# School_System.net
KiCad netlist of a schematic drawn in EAGLE
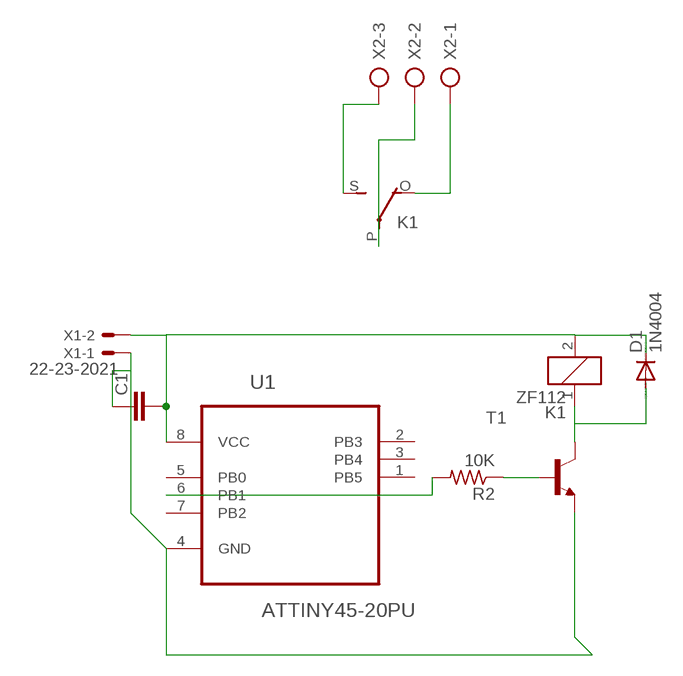
[diagram p0: schematic, sheet 1]

(export (version "E")
  (design (tool "Eeschema 10.0.6"))
  (components
    (comp (ref "C1")
      (value "C2,5-3")
      (footprint "eagle-import:C2.5-3")
      (libsource (lib "eagle-import") (part "C2,5-3"))
    )
    (comp (ref "D1")
      (value "1N4004")
      (footprint "eagle-import:DO41-10")
      (libsource (lib "eagle-import") (part "1N4004"))
    )
    (comp (ref "K1")
      (value "ZF112")
      (footprint "eagle-import:ZF112")
      (libsource (lib "eagle-import") (part "ZF112"))
    )
    (comp (ref "R2")
      (value "10K")
      (footprint "eagle-import:0204_7")
      (libsource (lib "eagle-import") (part "R-US_0204/7"))
    )
    (comp (ref "T1")
      (value "2N2222-NPN-TO92-EBC")
      (footprint "eagle-import:TO92-EBC")
      (libsource (lib "eagle-import") (part "-NPN-TO92-EBC2N2222"))
    )
    (comp (ref "U1")
      (value "ATTINY45-20PU")
      (footprint "eagle-import:DIP254P762X533-8")
      (libsource (lib "eagle-import") (part "ATTINY45-20PU"))
    )
    (comp (ref "X1")
      (value "22-23-2021")
      (footprint "eagle-import:22-23-2021")
      (fields (field (name "MF") "MOLEX"))
      (libsource (lib "eagle-import") (part "22-23-2021"))
    )
    (comp (ref "X2")
      (value "AK300/3")
      (footprint "eagle-import:AK300_3")
      (libsource (lib "eagle-import") (part "AK300/3"))
    )
  )
  (nets
    (net (code "1") (name "Net-(D1-PadA)") (class "Default")
      (node (ref "D1") (pin "A") (pinfunction "A_A") (pintype "passive"))
      (node (ref "K1") (pin "1") (pinfunction "1_1") (pintype "passive"))
      (node (ref "T1") (pin "C") (pinfunction "C_C") (pintype "passive"))
    )
    (net (code "2") (name "Net-(R2-Pad1)") (class "Default")
      (node (ref "R2") (pin "1") (pinfunction "1_1") (pintype "passive"))
      (node (ref "T1") (pin "B") (pinfunction "B_B") (pintype "passive"))
    )
    (net (code "3") (name "Net-(U1-GND)") (class "Default")
      (node (ref "C1") (pin "1") (pinfunction "1_1") (pintype "passive"))
      (node (ref "T1") (pin "E") (pinfunction "E_E") (pintype "passive"))
      (node (ref "U1") (pin "4") (pinfunction "GND_4") (pintype "passive"))
      (node (ref "X1") (pin "1") (pinfunction "S_1") (pintype "passive"))
    )
    (net (code "4") (name "Net-(U1-PB1)") (class "Default")
      (node (ref "R2") (pin "2") (pinfunction "2_2") (pintype "passive"))
      (node (ref "U1") (pin "6") (pinfunction "PB1_6") (pintype "bidirectional"))
    )
    (net (code "5") (name "Net-(U1-VCC)") (class "Default")
      (node (ref "C1") (pin "2") (pinfunction "2_2") (pintype "passive"))
      (node (ref "D1") (pin "C") (pinfunction "C_C") (pintype "passive"))
      (node (ref "K1") (pin "2") (pinfunction "2_2") (pintype "passive"))
      (node (ref "U1") (pin "8") (pinfunction "VCC_8") (pintype "power_in"))
      (node (ref "X1") (pin "2") (pinfunction "S_2") (pintype "passive"))
    )
    (net (code "6") (name "Net-(X2A-KL)") (class "Default")
      (node (ref "K1") (pin "O") (pinfunction "O_O") (pintype "passive"))
      (node (ref "X2") (pin "1") (pinfunction "KL_1") (pintype "passive"))
    )
    (net (code "7") (name "Net-(X2B-KL)") (class "Default")
      (node (ref "K1") (pin "P") (pinfunction "P_P") (pintype "passive"))
      (node (ref "X2") (pin "2") (pinfunction "KL_2") (pintype "passive"))
    )
    (net (code "8") (name "Net-(X2C-KL)") (class "Default")
      (node (ref "K1") (pin "S") (pinfunction "S_S") (pintype "passive"))
      (node (ref "X2") (pin "3") (pinfunction "KL_3") (pintype "passive"))
    )
    (net (code "9") (name "unconnected-(U1-PB0-Pad5)") (class "Default")
      (node (ref "U1") (pin "5") (pinfunction "PB0_5") (pintype "bidirectional"))
    )
    (net (code "10") (name "unconnected-(U1-PB2-Pad7)") (class "Default")
      (node (ref "U1") (pin "7") (pinfunction "PB2_7") (pintype "bidirectional"))
    )
    (net (code "11") (name "unconnected-(U1-PB3-Pad2)") (class "Default")
      (node (ref "U1") (pin "2") (pinfunction "PB3_2") (pintype "bidirectional"))
    )
    (net (code "12") (name "unconnected-(U1-PB4-Pad3)") (class "Default")
      (node (ref "U1") (pin "3") (pinfunction "PB4_3") (pintype "bidirectional"))
    )
    (net (code "13") (name "unconnected-(U1-PB5-Pad1)") (class "Default")
      (node (ref "U1") (pin "1") (pinfunction "PB5_1") (pintype "bidirectional"))
    )
  )
)
